# ESP32_CLOCK_v1.net
KiCad netlist of a schematic drawn in EAGLE
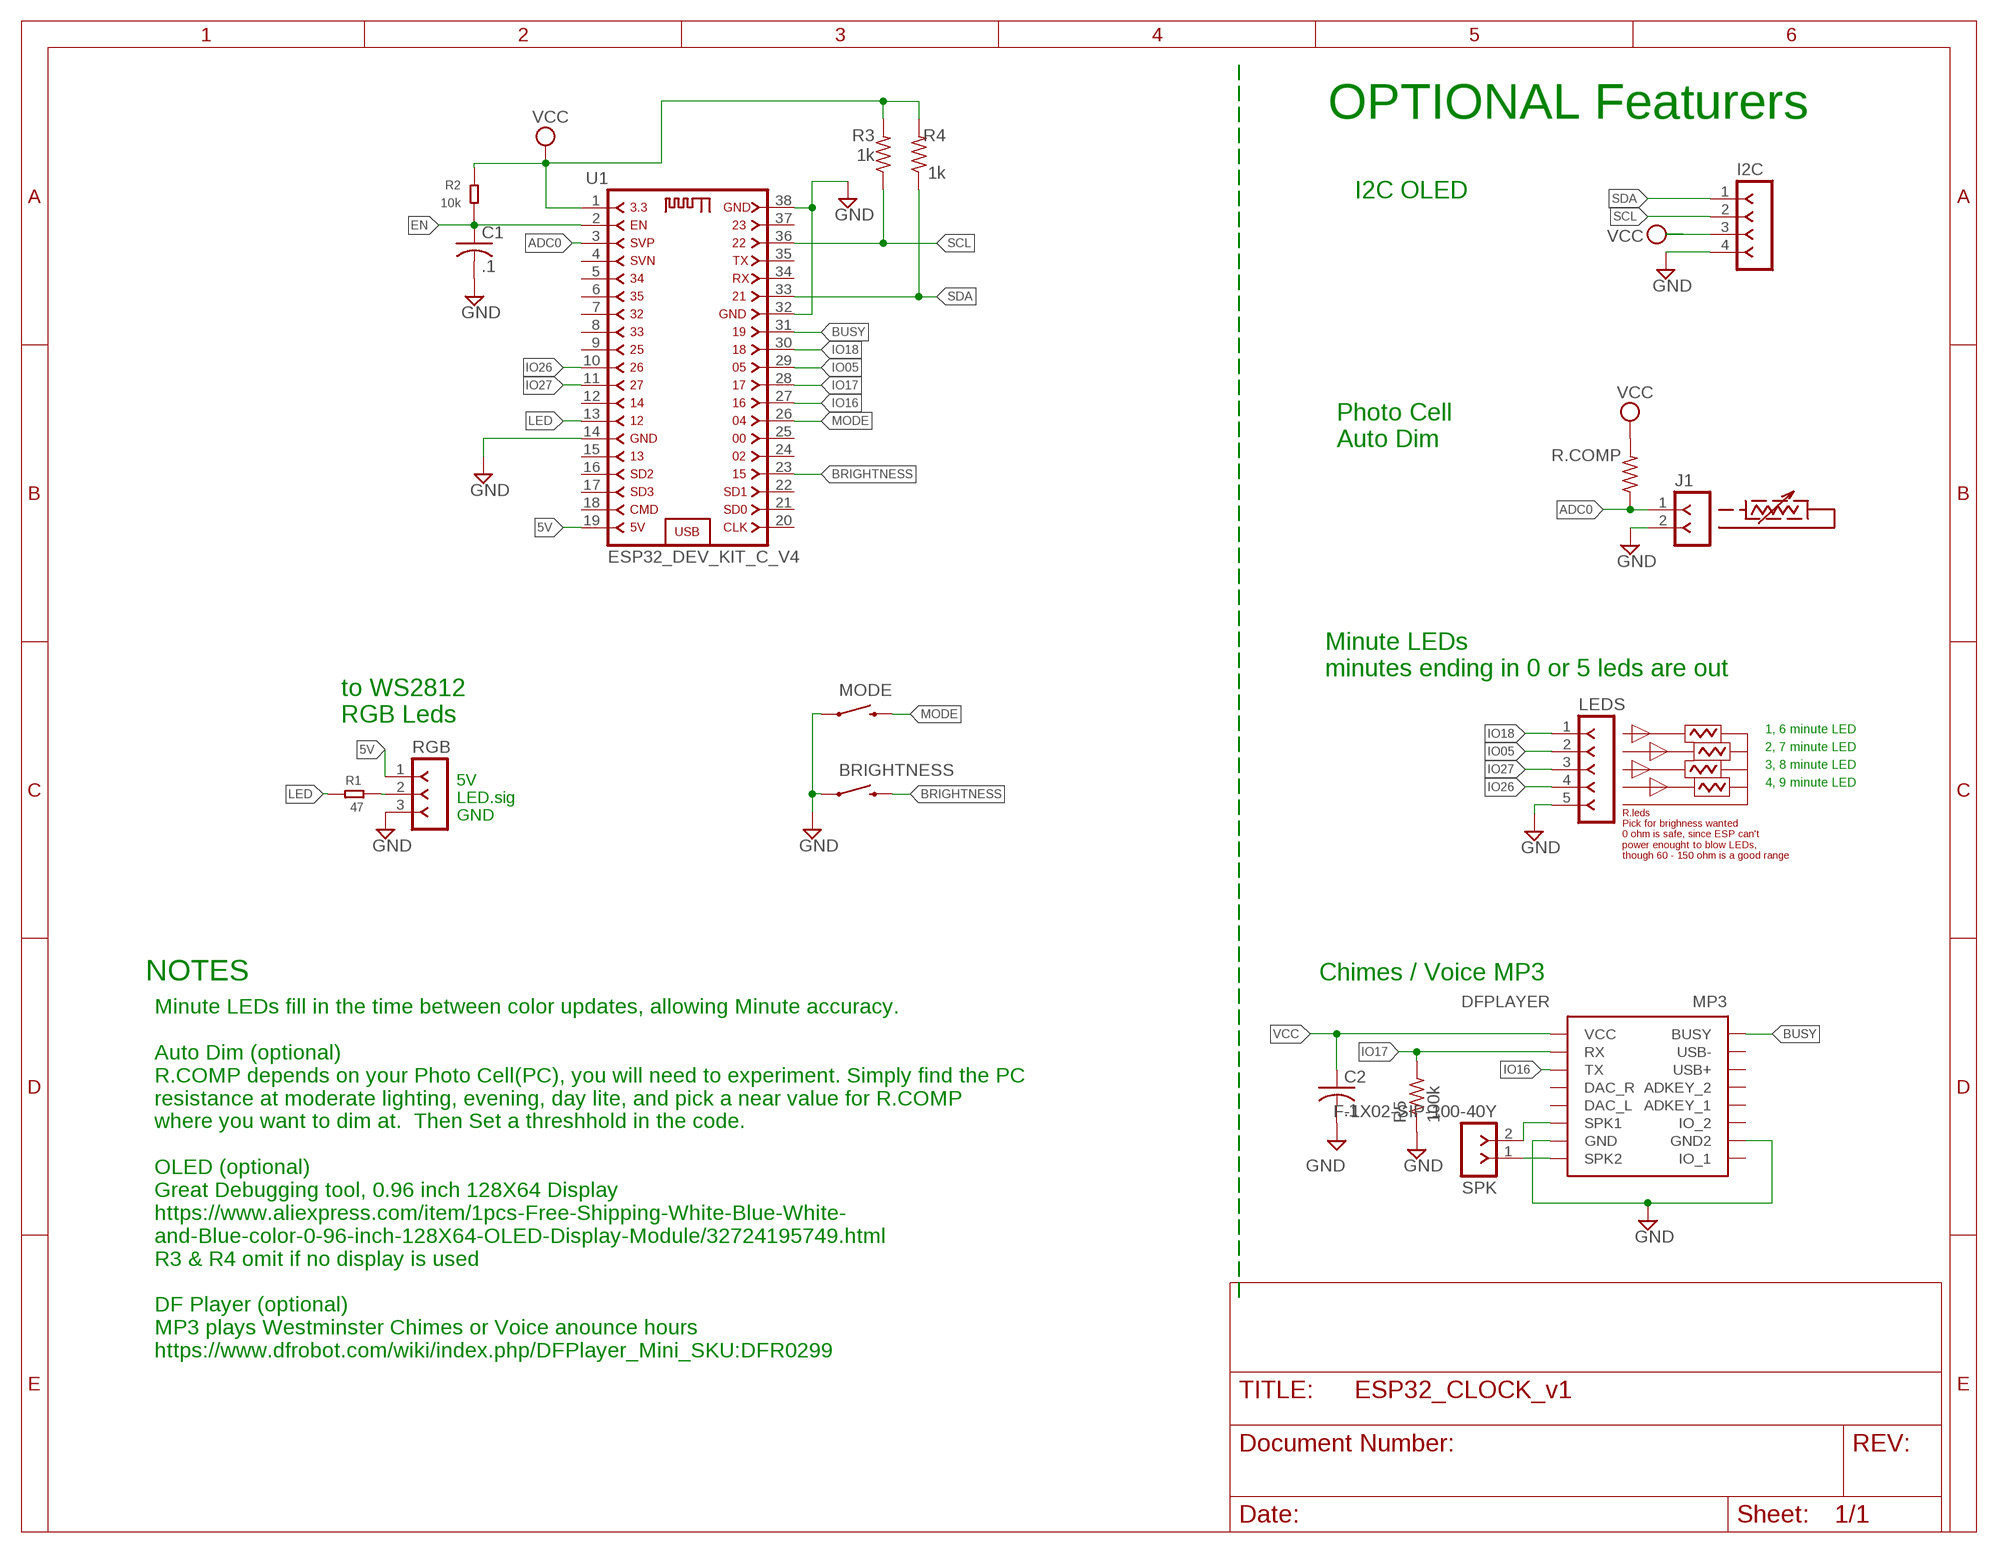
[diagram p0: schematic, sheet 1]

(export (version "E")
  (design (tool "Eeschema 10.0.6"))
  (components
    (comp (ref "BRIGHTNESS")
      (value "SWITCH-MOMENTARY-2SIDE_EZ")
      (footprint "eagle-import:TACTILE-PTH-SIDEEZ")
      (libsource (lib "eagle-import") (part "SWITCH-MOMENTARY-2SIDE_EZ"))
    )
    (comp (ref "C1")
      (value ".1")
      (footprint "eagle-import:C0805K")
      (libsource (lib "eagle-import") (part "C-USC0805K"))
    )
    (comp (ref "C2")
      (value ".1")
      (footprint "eagle-import:C0805K")
      (libsource (lib "eagle-import") (part "C-USC0805K"))
    )
    (comp (ref "I2C")
      (value "F-1X04-SIP-100-40Y")
      (footprint "eagle-import:SIP-100-04-40Y")
      (libsource (lib "eagle-import") (part "F-1X04-SIP-100-40Y"))
    )
    (comp (ref "J1")
      (value "F-1X02-SIP-100-40Y")
      (footprint "eagle-import:SIP-100-02-40Y")
      (libsource (lib "eagle-import") (part "F-1X02-SIP-100-40Y"))
    )
    (comp (ref "LEDS")
      (value "F-1X05-SIP-100-40Y")
      (footprint "eagle-import:SIP-100-05-40Y")
      (libsource (lib "eagle-import") (part "F-1X05-SIP-100-40Y"))
    )
    (comp (ref "MODE")
      (value "SWITCH-MOMENTARY-2SIDE_EZ")
      (footprint "eagle-import:TACTILE-PTH-SIDEEZ")
      (libsource (lib "eagle-import") (part "SWITCH-MOMENTARY-2SIDE_EZ"))
    )
    (comp (ref "MP3")
      (value "DFPLAYER")
      (footprint "eagle-import:DFPLAYER")
      (libsource (lib "eagle-import") (part "DFPLAYER"))
    )
    (comp (ref "R.COMP")
      (value "R-US_M0805")
      (footprint "eagle-import:M0805")
      (libsource (lib "eagle-import") (part "R-US_M0805"))
    )
    (comp (ref "R1")
      (value "47")
      (footprint "eagle-import:R0805")
      (libsource (lib "eagle-import") (part "R-0805"))
    )
    (comp (ref "R2")
      (value "10k")
      (footprint "eagle-import:R0805")
      (libsource (lib "eagle-import") (part "R-0805"))
    )
    (comp (ref "R3")
      (value "1k")
      (footprint "eagle-import:M0805")
      (libsource (lib "eagle-import") (part "R-US_M0805"))
    )
    (comp (ref "R4")
      (value "1k")
      (footprint "eagle-import:M0805")
      (libsource (lib "eagle-import") (part "R-US_M0805"))
    )
    (comp (ref "R5")
      (value "100k")
      (footprint "eagle-import:M0805")
      (libsource (lib "eagle-import") (part "R-US_M0805"))
    )
    (comp (ref "RGB")
      (value "F-1X03-SIP-100-40Y")
      (footprint "eagle-import:SIP-100-03-40Y")
      (libsource (lib "eagle-import") (part "F-1X03-SIP-100-40Y"))
    )
    (comp (ref "SPK")
      (value "F-1X02-SIP-100-40Y")
      (footprint "eagle-import:SIP-100-02-40Y")
      (libsource (lib "eagle-import") (part "F-1X02-SIP-100-40Y"))
    )
    (comp (ref "U1")
      (value "ESP32_DEV_KIT_C_V4")
      (footprint "eagle-import:ESP32_DEV_KIT_C_V4")
      (libsource (lib "eagle-import") (part "ESP32_DEV_KIT_C_V4"))
    )
  )
  (nets
    (net (code "1") (name "5V") (class "Default")
      (node (ref "RGB") (pin "1") (pinfunction "1_1") (pintype "passive"))
      (node (ref "U1") (pin "19") (pinfunction "19_19") (pintype "passive"))
    )
    (net (code "2") (name "ADC0") (class "Default")
      (node (ref "J1") (pin "1") (pinfunction "1_1") (pintype "passive"))
      (node (ref "R.COMP") (pin "1") (pinfunction "1_1") (pintype "passive"))
      (node (ref "U1") (pin "3") (pinfunction "3_3") (pintype "passive"))
    )
    (net (code "3") (name "BRIGHTNESS") (class "Default")
      (node (ref "BRIGHTNESS") (pin "2") (pinfunction "2_2") (pintype "passive"))
      (node (ref "U1") (pin "23") (pinfunction "23_23") (pintype "passive"))
    )
    (net (code "4") (name "BUSY") (class "Default")
      (node (ref "MP3") (pin "BUSY") (pinfunction "BUSY_BUSY") (pintype "bidirectional"))
      (node (ref "U1") (pin "31") (pinfunction "31_31") (pintype "passive"))
    )
    (net (code "5") (name "EN") (class "Default")
      (node (ref "C1") (pin "1") (pinfunction "1_1") (pintype "passive"))
      (node (ref "R2") (pin "1") (pinfunction "1_1") (pintype "passive"))
      (node (ref "U1") (pin "2") (pinfunction "2_2") (pintype "passive"))
    )
    (net (code "6") (name "GND") (class "Default")
      (node (ref "BRIGHTNESS") (pin "1") (pinfunction "1_1") (pintype "passive"))
      (node (ref "C1") (pin "2") (pinfunction "2_2") (pintype "passive"))
      (node (ref "C2") (pin "2") (pinfunction "2_2") (pintype "passive"))
      (node (ref "I2C") (pin "4") (pinfunction "4_4") (pintype "passive"))
      (node (ref "J1") (pin "2") (pinfunction "2_2") (pintype "passive"))
      (node (ref "LEDS") (pin "5") (pinfunction "5_5") (pintype "passive"))
      (node (ref "MODE") (pin "1") (pinfunction "1_1") (pintype "passive"))
      (node (ref "MP3") (pin "GND") (pinfunction "GND_GND") (pintype "bidirectional"))
      (node (ref "MP3") (pin "GND2") (pinfunction "GND2_GND2") (pintype "bidirectional"))
      (node (ref "R5") (pin "1") (pinfunction "1_1") (pintype "passive"))
      (node (ref "RGB") (pin "3") (pinfunction "3_3") (pintype "passive"))
      (node (ref "U1") (pin "14") (pinfunction "14_14") (pintype "passive"))
      (node (ref "U1") (pin "32") (pinfunction "32_32") (pintype "passive"))
      (node (ref "U1") (pin "38") (pinfunction "38_38") (pintype "passive"))
    )
    (net (code "7") (name "IO05") (class "Default")
      (node (ref "LEDS") (pin "2") (pinfunction "2_2") (pintype "passive"))
      (node (ref "U1") (pin "29") (pinfunction "29_29") (pintype "passive"))
    )
    (net (code "8") (name "IO16") (class "Default")
      (node (ref "MP3") (pin "TX") (pinfunction "TX_TX") (pintype "bidirectional"))
      (node (ref "U1") (pin "27") (pinfunction "27_27") (pintype "passive"))
    )
    (net (code "9") (name "IO17") (class "Default")
      (node (ref "MP3") (pin "RX") (pinfunction "RX_RX") (pintype "bidirectional"))
      (node (ref "R5") (pin "2") (pinfunction "2_2") (pintype "passive"))
      (node (ref "U1") (pin "28") (pinfunction "28_28") (pintype "passive"))
    )
    (net (code "10") (name "IO18") (class "Default")
      (node (ref "LEDS") (pin "1") (pinfunction "1_1") (pintype "passive"))
      (node (ref "U1") (pin "30") (pinfunction "30_30") (pintype "passive"))
    )
    (net (code "11") (name "IO26") (class "Default")
      (node (ref "LEDS") (pin "4") (pinfunction "4_4") (pintype "passive"))
      (node (ref "U1") (pin "10") (pinfunction "10_10") (pintype "passive"))
    )
    (net (code "12") (name "IO27") (class "Default")
      (node (ref "LEDS") (pin "3") (pinfunction "3_3") (pintype "passive"))
      (node (ref "U1") (pin "11") (pinfunction "11_11") (pintype "passive"))
    )
    (net (code "13") (name "LED") (class "Default")
      (node (ref "R1") (pin "2") (pinfunction "2_2") (pintype "passive"))
      (node (ref "U1") (pin "13") (pinfunction "13_13") (pintype "passive"))
    )
    (net (code "14") (name "MODE") (class "Default")
      (node (ref "MODE") (pin "2") (pinfunction "2_2") (pintype "passive"))
      (node (ref "U1") (pin "26") (pinfunction "26_26") (pintype "passive"))
    )
    (net (code "15") (name "Net-(MP3-PadSPK1)") (class "Default")
      (node (ref "MP3") (pin "SPK1") (pinfunction "SPK1_SPK1") (pintype "bidirectional"))
      (node (ref "SPK") (pin "2") (pinfunction "2_2") (pintype "passive"))
    )
    (net (code "16") (name "Net-(MP3-PadSPK2)") (class "Default")
      (node (ref "MP3") (pin "SPK2") (pinfunction "SPK2_SPK2") (pintype "bidirectional"))
      (node (ref "SPK") (pin "1") (pinfunction "1_1") (pintype "passive"))
    )
    (net (code "17") (name "Net-(R1-Pad1)") (class "Default")
      (node (ref "R1") (pin "1") (pinfunction "1_1") (pintype "passive"))
      (node (ref "RGB") (pin "2") (pinfunction "2_2") (pintype "passive"))
    )
    (net (code "18") (name "SCL") (class "Default")
      (node (ref "I2C") (pin "2") (pinfunction "2_2") (pintype "passive"))
      (node (ref "R3") (pin "1") (pinfunction "1_1") (pintype "passive"))
      (node (ref "U1") (pin "36") (pinfunction "36_36") (pintype "passive"))
    )
    (net (code "19") (name "SDA") (class "Default")
      (node (ref "I2C") (pin "1") (pinfunction "1_1") (pintype "passive"))
      (node (ref "R4") (pin "1") (pinfunction "1_1") (pintype "passive"))
      (node (ref "U1") (pin "33") (pinfunction "33_33") (pintype "passive"))
    )
    (net (code "20") (name "VCC") (class "Default")
      (node (ref "C2") (pin "1") (pinfunction "1_1") (pintype "passive"))
      (node (ref "I2C") (pin "3") (pinfunction "3_3") (pintype "passive"))
      (node (ref "MP3") (pin "VCC") (pinfunction "VCC_VCC") (pintype "bidirectional"))
      (node (ref "R.COMP") (pin "2") (pinfunction "2_2") (pintype "passive"))
      (node (ref "R2") (pin "2") (pinfunction "2_2") (pintype "passive"))
      (node (ref "R3") (pin "2") (pinfunction "2_2") (pintype "passive"))
      (node (ref "R4") (pin "2") (pinfunction "2_2") (pintype "passive"))
      (node (ref "U1") (pin "1") (pinfunction "1_1") (pintype "passive"))
    )
    (net (code "21") (name "unconnected-(MP3-IO_1-PadIO1)") (class "Default")
      (node (ref "MP3") (pin "IO1") (pinfunction "IO_1_IO1") (pintype "bidirectional"))
    )
    (net (code "22") (name "unconnected-(MP3-PadADKEY_1)") (class "Default")
      (node (ref "MP3") (pin "ADKEY_1") (pinfunction "ADKEY_1_ADKEY_1") (pintype "bidirectional"))
    )
    (net (code "23") (name "unconnected-(MP3-PadADKEY_2)") (class "Default")
      (node (ref "MP3") (pin "ADKEY_2") (pinfunction "ADKEY_2_ADKEY_2") (pintype "bidirectional"))
    )
    (net (code "24") (name "unconnected-(MP3-PadDAC_L)") (class "Default")
      (node (ref "MP3") (pin "DAC_L") (pinfunction "DAC_L_DAC_L") (pintype "bidirectional"))
    )
    (net (code "25") (name "unconnected-(MP3-PadDAC_R)") (class "Default")
      (node (ref "MP3") (pin "DAC_R") (pinfunction "DAC_R_DAC_R") (pintype "bidirectional"))
    )
    (net (code "26") (name "unconnected-(MP3-PadIO_2)") (class "Default")
      (node (ref "MP3") (pin "IO_2") (pinfunction "IO_2_IO_2") (pintype "bidirectional"))
    )
    (net (code "27") (name "unconnected-(MP3-PadUSB+)") (class "Default")
      (node (ref "MP3") (pin "USB+") (pinfunction "USB+_USB+") (pintype "bidirectional"))
    )
    (net (code "28") (name "unconnected-(MP3-PadUSB-)") (class "Default")
      (node (ref "MP3") (pin "USB-") (pinfunction "USB-_USB-") (pintype "bidirectional"))
    )
    (net (code "29") (name "unconnected-(U1-Pad4)") (class "Default")
      (node (ref "U1") (pin "4") (pinfunction "4_4") (pintype "passive"))
    )
    (net (code "30") (name "unconnected-(U1-Pad5)") (class "Default")
      (node (ref "U1") (pin "5") (pinfunction "5_5") (pintype "passive"))
    )
    (net (code "31") (name "unconnected-(U1-Pad6)") (class "Default")
      (node (ref "U1") (pin "6") (pinfunction "6_6") (pintype "passive"))
    )
    (net (code "32") (name "unconnected-(U1-Pad7)") (class "Default")
      (node (ref "U1") (pin "7") (pinfunction "7_7") (pintype "passive"))
    )
    (net (code "33") (name "unconnected-(U1-Pad8)") (class "Default")
      (node (ref "U1") (pin "8") (pinfunction "8_8") (pintype "passive"))
    )
    (net (code "34") (name "unconnected-(U1-Pad9)") (class "Default")
      (node (ref "U1") (pin "9") (pinfunction "9_9") (pintype "passive"))
    )
    (net (code "35") (name "unconnected-(U1-Pad12)") (class "Default")
      (node (ref "U1") (pin "12") (pinfunction "12_12") (pintype "passive"))
    )
    (net (code "36") (name "unconnected-(U1-Pad15)") (class "Default")
      (node (ref "U1") (pin "15") (pinfunction "15_15") (pintype "passive"))
    )
    (net (code "37") (name "unconnected-(U1-Pad16)") (class "Default")
      (node (ref "U1") (pin "16") (pinfunction "16_16") (pintype "passive"))
    )
    (net (code "38") (name "unconnected-(U1-Pad17)") (class "Default")
      (node (ref "U1") (pin "17") (pinfunction "17_17") (pintype "passive"))
    )
    (net (code "39") (name "unconnected-(U1-Pad18)") (class "Default")
      (node (ref "U1") (pin "18") (pinfunction "18_18") (pintype "passive"))
    )
    (net (code "40") (name "unconnected-(U1-Pad20)") (class "Default")
      (node (ref "U1") (pin "20") (pinfunction "20_20") (pintype "passive"))
    )
    (net (code "41") (name "unconnected-(U1-Pad21)") (class "Default")
      (node (ref "U1") (pin "21") (pinfunction "21_21") (pintype "passive"))
    )
    (net (code "42") (name "unconnected-(U1-Pad22)") (class "Default")
      (node (ref "U1") (pin "22") (pinfunction "22_22") (pintype "passive"))
    )
    (net (code "43") (name "unconnected-(U1-Pad24)") (class "Default")
      (node (ref "U1") (pin "24") (pinfunction "24_24") (pintype "passive"))
    )
    (net (code "44") (name "unconnected-(U1-Pad25)") (class "Default")
      (node (ref "U1") (pin "25") (pinfunction "25_25") (pintype "passive"))
    )
    (net (code "45") (name "unconnected-(U1-Pad34)") (class "Default")
      (node (ref "U1") (pin "34") (pinfunction "34_34") (pintype "passive"))
    )
    (net (code "46") (name "unconnected-(U1-Pad35)") (class "Default")
      (node (ref "U1") (pin "35") (pinfunction "35_35") (pintype "passive"))
    )
    (net (code "47") (name "unconnected-(U1-Pad37)") (class "Default")
      (node (ref "U1") (pin "37") (pinfunction "37_37") (pintype "passive"))
    )
  )
)
